# VisualightMicroDIY_032_gnd.net
KiCad netlist of a schematic drawn in EAGLE
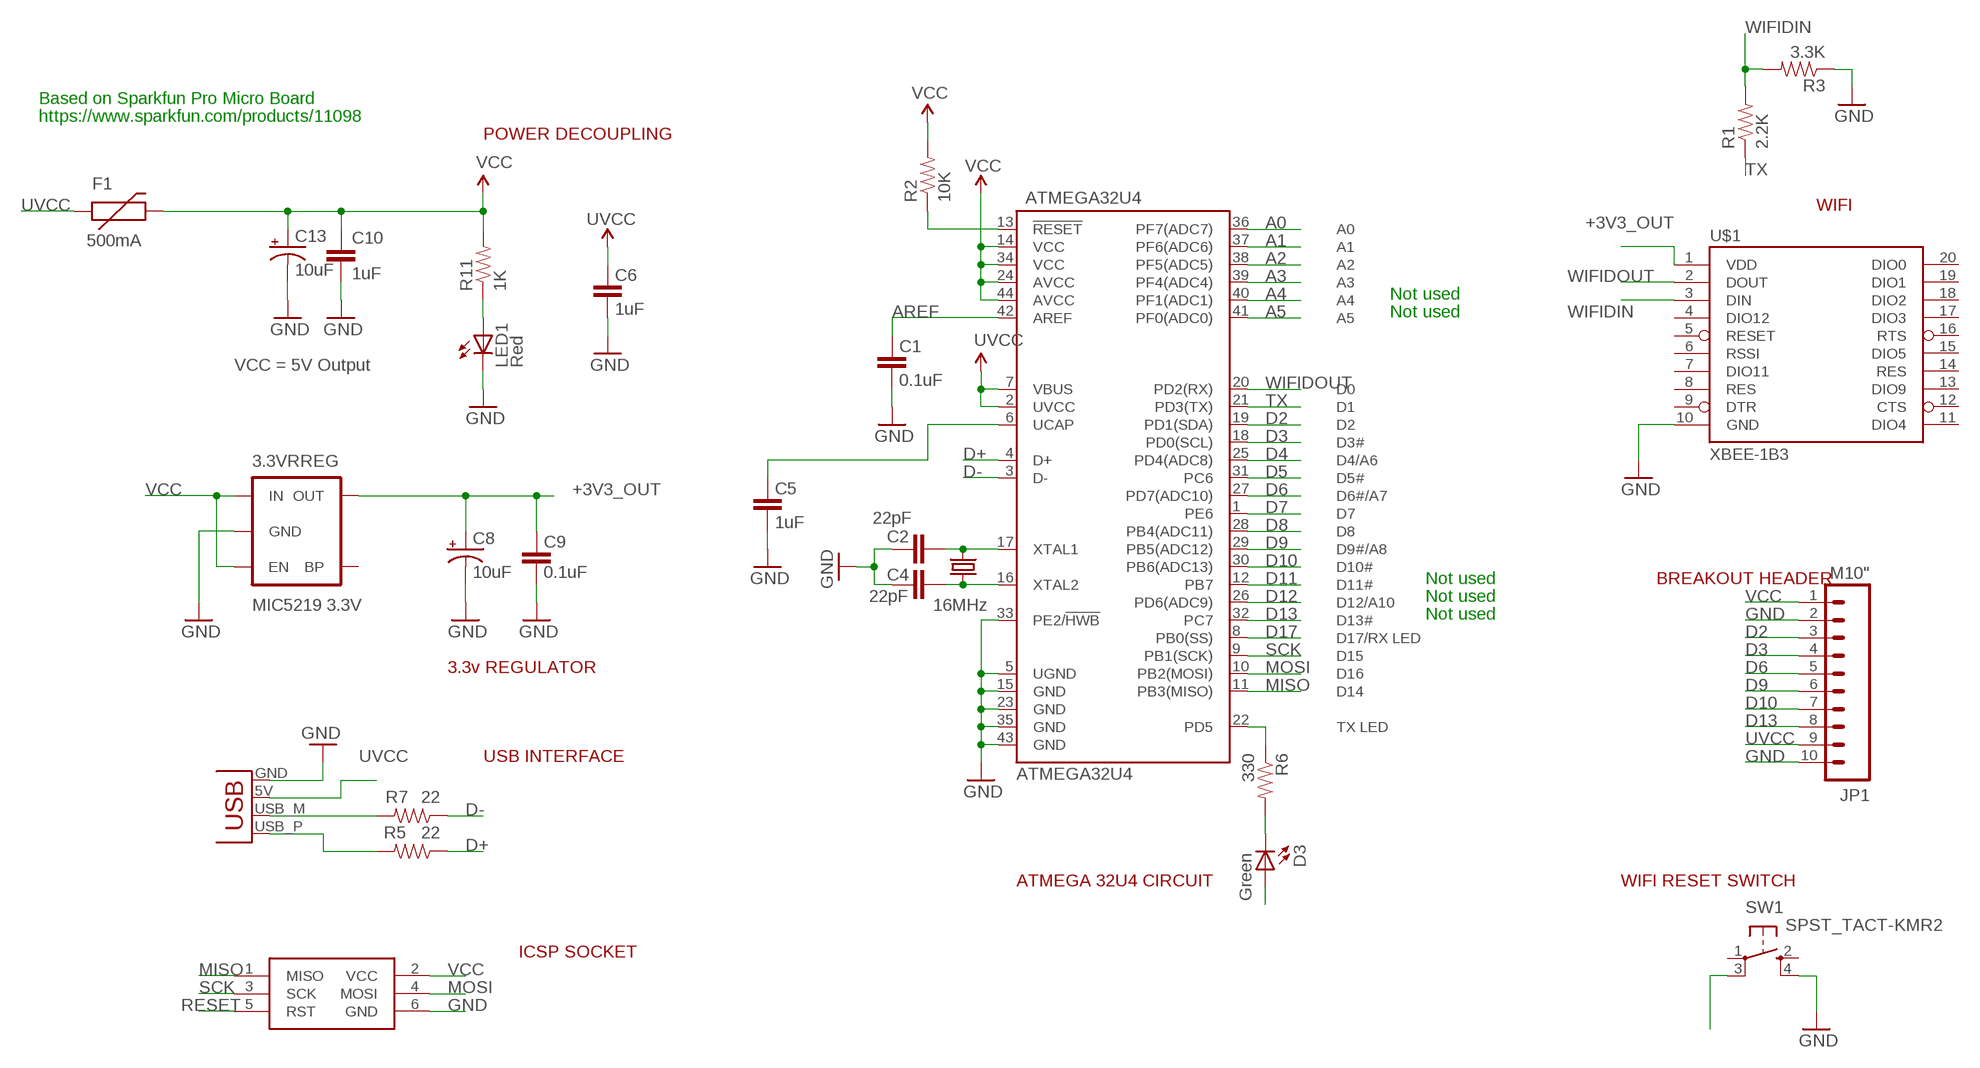
[diagram p0: schematic, sheet 1]

(export (version "E")
  (design (tool "Eeschema 10.0.6"))
  (components
    (comp (ref "3.3VRREG")
      (value "MIC5219 3.3V")
      (footprint "eagle-import:SOT23-5")
      (libsource (lib "eagle-import") (part "V_REG_MIC52193.3V"))
    )
    (comp (ref "ATMEGA32U4")
      (value "ATMEGA32U4")
      (footprint "eagle-import:SPARKFUN-DIGITALIC_TQFP44")
      (libsource (lib "eagle-import") (part "ATMEGA32U4TQFP"))
    )
    (comp (ref "C1")
      (value "0.1uF")
      (footprint "eagle-import:0402-CAP")
      (libsource (lib "eagle-import") (part "CAP0402-CAP"))
    )
    (comp (ref "C2")
      (value "22pF")
      (footprint "eagle-import:0402-CAP")
      (libsource (lib "eagle-import") (part "CAP0402-CAP"))
    )
    (comp (ref "C4")
      (value "22pF")
      (footprint "eagle-import:0402-CAP")
      (libsource (lib "eagle-import") (part "CAP0402-CAP"))
    )
    (comp (ref "C5")
      (value "1uF")
      (footprint "eagle-import:0402-CAP")
      (libsource (lib "eagle-import") (part "CAP0402-CAP"))
    )
    (comp (ref "C6")
      (value "1uF")
      (footprint "eagle-import:0402-CAP")
      (libsource (lib "eagle-import") (part "CAP0402-CAP"))
    )
    (comp (ref "C8")
      (value "10uF")
      (footprint "eagle-import:EIA3216")
      (libsource (lib "eagle-import") (part "CAP_POL1206"))
    )
    (comp (ref "C9")
      (value "0.1uF")
      (footprint "eagle-import:0402-CAP")
      (libsource (lib "eagle-import") (part "CAP0402-CAP"))
    )
    (comp (ref "C10")
      (value "1uF")
      (footprint "eagle-import:0402-CAP")
      (libsource (lib "eagle-import") (part "CAP0402-CAP"))
    )
    (comp (ref "C13")
      (value "10uF")
      (footprint "eagle-import:EIA3216")
      (libsource (lib "eagle-import") (part "CAP_POL1206"))
    )
    (comp (ref "D3")
      (value "Green")
      (footprint "eagle-import:LED-0603")
      (libsource (lib "eagle-import") (part "LED0603"))
    )
    (comp (ref "F1")
      (value "500mA")
      (footprint "eagle-import:PTC-1206")
      (libsource (lib "eagle-import") (part "PTCSMD"))
    )
    (comp (ref "ISP1")
      (value "AVRISP-6")
      (footprint "eagle-import:AVRISP")
      (libsource (lib "eagle-import") (part "AVRISP-6"))
    )
    (comp (ref "JP1")
      (value "M10\"")
      (footprint "eagle-import:1X10")
      (libsource (lib "eagle-import") (part "M10{dblquote}"))
    )
    (comp (ref "LED1")
      (value "Red")
      (footprint "eagle-import:LED-0603")
      (libsource (lib "eagle-import") (part "LED0603"))
    )
    (comp (ref "R1")
      (value "2.2K")
      (footprint "eagle-import:0402-RES")
      (libsource (lib "eagle-import") (part "RESISTOR0402-RES"))
    )
    (comp (ref "R2")
      (value "10K")
      (footprint "eagle-import:0402-RES")
      (libsource (lib "eagle-import") (part "RESISTOR0402-RES"))
    )
    (comp (ref "R3")
      (value "3.3K")
      (footprint "eagle-import:0402-RES")
      (libsource (lib "eagle-import") (part "RESISTOR0402-RES"))
    )
    (comp (ref "R5")
      (value "22")
      (footprint "eagle-import:0402-RES")
      (libsource (lib "eagle-import") (part "RESISTOR0402-RES"))
    )
    (comp (ref "R6")
      (value "330")
      (footprint "eagle-import:0402-RES")
      (libsource (lib "eagle-import") (part "RESISTOR0402-RES"))
    )
    (comp (ref "R7")
      (value "22")
      (footprint "eagle-import:0402-RES")
      (libsource (lib "eagle-import") (part "RESISTOR0402-RES"))
    )
    (comp (ref "R11")
      (value "1K")
      (footprint "eagle-import:0402-RES")
      (libsource (lib "eagle-import") (part "RESISTOR0402-RES"))
    )
    (comp (ref "SW1")
      (value "SPST_TACT-KMR2")
      (footprint "eagle-import:KMR2")
      (libsource (lib "eagle-import") (part "SPST_TACT-KMR2"))
    )
    (comp (ref "U$1")
      (value "XBEE-1B3")
      (footprint "eagle-import:XBEE-SMD")
      (libsource (lib "eagle-import") (part "XBEE-1B3"))
    )
    (comp (ref "X2")
      (value "USBPCB")
      (footprint "eagle-import:USB-A-PCB")
      (libsource (lib "eagle-import") (part "USBPCB"))
    )
    (comp (ref "Y1")
      (value "16MHz")
      (footprint "eagle-import:CRYSTAL-SMD-5X3")
      (libsource (lib "eagle-import") (part "CRYSTAL5X3"))
    )
  )
  (nets
    (net (code "1") (name "/+3V3_OUT") (class "Default")
      (node (ref "3.3VRREG") (pin "5") (pinfunction "OUT_5") (pintype "passive"))
      (node (ref "C8") (pin "A") (pinfunction "+_A") (pintype "passive"))
      (node (ref "C9") (pin "2") (pinfunction "2_2") (pintype "passive"))
      (node (ref "U$1") (pin "1") (pinfunction "VDD_1") (pintype "power_in"))
    )
    (net (code "2") (name "/A0") (class "Default")
      (node (ref "ATMEGA32U4") (pin "36") (pinfunction "PF7(ADC7)_36") (pintype "bidirectional"))
    )
    (net (code "3") (name "/A1") (class "Default")
      (node (ref "ATMEGA32U4") (pin "37") (pinfunction "PF6(ADC6)_37") (pintype "bidirectional"))
    )
    (net (code "4") (name "/A2") (class "Default")
      (node (ref "ATMEGA32U4") (pin "38") (pinfunction "PF5(ADC5)_38") (pintype "bidirectional"))
    )
    (net (code "5") (name "/A3") (class "Default")
      (node (ref "ATMEGA32U4") (pin "39") (pinfunction "PF4(ADC4)_39") (pintype "bidirectional"))
    )
    (net (code "6") (name "/A4") (class "Default")
      (node (ref "ATMEGA32U4") (pin "40") (pinfunction "PF1(ADC1)_40") (pintype "bidirectional"))
    )
    (net (code "7") (name "/A5") (class "Default")
      (node (ref "ATMEGA32U4") (pin "41") (pinfunction "PF0(ADC0)_41") (pintype "bidirectional"))
    )
    (net (code "8") (name "/AREF") (class "Default")
      (node (ref "ATMEGA32U4") (pin "42") (pinfunction "AREF_42") (pintype "bidirectional"))
      (node (ref "C1") (pin "2") (pinfunction "2_2") (pintype "passive"))
    )
    (net (code "9") (name "/D+") (class "Default")
      (node (ref "ATMEGA32U4") (pin "4") (pinfunction "D+_4") (pintype "bidirectional"))
      (node (ref "R5") (pin "1") (pinfunction "1_1") (pintype "passive"))
    )
    (net (code "10") (name "/D-") (class "Default")
      (node (ref "ATMEGA32U4") (pin "3") (pinfunction "D-_3") (pintype "bidirectional"))
      (node (ref "R7") (pin "1") (pinfunction "1_1") (pintype "passive"))
    )
    (net (code "11") (name "/D2") (class "Default")
      (node (ref "ATMEGA32U4") (pin "19") (pinfunction "PD1(SDA)_19") (pintype "bidirectional"))
      (node (ref "JP1") (pin "3") (pinfunction "3_3") (pintype "passive"))
    )
    (net (code "12") (name "/D3") (class "Default")
      (node (ref "ATMEGA32U4") (pin "18") (pinfunction "PD0(SCL)_18") (pintype "bidirectional"))
      (node (ref "JP1") (pin "4") (pinfunction "4_4") (pintype "passive"))
    )
    (net (code "13") (name "/D4") (class "Default")
      (node (ref "ATMEGA32U4") (pin "25") (pinfunction "PD4(ADC8)_25") (pintype "bidirectional"))
    )
    (net (code "14") (name "/D5") (class "Default")
      (node (ref "ATMEGA32U4") (pin "31") (pinfunction "PC6_31") (pintype "bidirectional"))
    )
    (net (code "15") (name "/D6") (class "Default")
      (node (ref "ATMEGA32U4") (pin "27") (pinfunction "PD7(ADC10)_27") (pintype "bidirectional"))
      (node (ref "JP1") (pin "5") (pinfunction "5_5") (pintype "passive"))
    )
    (net (code "16") (name "/D7") (class "Default")
      (node (ref "ATMEGA32U4") (pin "1") (pinfunction "PE6_1") (pintype "bidirectional"))
      (node (ref "SW1") (pin "3") (pinfunction "P1_3") (pintype "passive"))
    )
    (net (code "17") (name "/D8") (class "Default")
      (node (ref "ATMEGA32U4") (pin "28") (pinfunction "PB4(ADC11)_28") (pintype "bidirectional"))
    )
    (net (code "18") (name "/D9") (class "Default")
      (node (ref "ATMEGA32U4") (pin "29") (pinfunction "PB5(ADC12)_29") (pintype "bidirectional"))
      (node (ref "JP1") (pin "6") (pinfunction "6_6") (pintype "passive"))
    )
    (net (code "19") (name "/D10") (class "Default")
      (node (ref "ATMEGA32U4") (pin "30") (pinfunction "PB6(ADC13)_30") (pintype "bidirectional"))
      (node (ref "JP1") (pin "7") (pinfunction "7_7") (pintype "passive"))
    )
    (net (code "20") (name "/D11") (class "Default")
      (node (ref "ATMEGA32U4") (pin "12") (pinfunction "PB7_12") (pintype "bidirectional"))
    )
    (net (code "21") (name "/D12") (class "Default")
      (node (ref "ATMEGA32U4") (pin "26") (pinfunction "PD6(ADC9)_26") (pintype "bidirectional"))
    )
    (net (code "22") (name "/D13") (class "Default")
      (node (ref "ATMEGA32U4") (pin "32") (pinfunction "PC7_32") (pintype "bidirectional"))
      (node (ref "JP1") (pin "8") (pinfunction "8_8") (pintype "passive"))
    )
    (net (code "23") (name "/D17") (class "Default")
      (node (ref "ATMEGA32U4") (pin "8") (pinfunction "PB0(SS)_8") (pintype "bidirectional"))
    )
    (net (code "24") (name "/MISO") (class "Default")
      (node (ref "ATMEGA32U4") (pin "11") (pinfunction "PB3(MISO)_11") (pintype "bidirectional"))
      (node (ref "ISP1") (pin "1") (pinfunction "MISO_1") (pintype "input"))
    )
    (net (code "25") (name "/MOSI") (class "Default")
      (node (ref "ATMEGA32U4") (pin "10") (pinfunction "PB2(MOSI)_10") (pintype "bidirectional"))
      (node (ref "ISP1") (pin "4") (pinfunction "MOSI_4") (pintype "output"))
    )
    (net (code "26") (name "/RESET") (class "Default")
      (node (ref "ATMEGA32U4") (pin "13") (pinfunction "~{RESET}_13") (pintype "bidirectional"))
      (node (ref "ISP1") (pin "5") (pinfunction "RST_5") (pintype "output"))
      (node (ref "R2") (pin "1") (pinfunction "1_1") (pintype "passive"))
    )
    (net (code "27") (name "/SCK") (class "Default")
      (node (ref "ATMEGA32U4") (pin "9") (pinfunction "PB1(SCK)_9") (pintype "bidirectional"))
      (node (ref "ISP1") (pin "3") (pinfunction "SCK_3") (pintype "output"))
    )
    (net (code "28") (name "/TX") (class "Default")
      (node (ref "ATMEGA32U4") (pin "21") (pinfunction "PD3(TX)_21") (pintype "bidirectional"))
      (node (ref "R1") (pin "1") (pinfunction "1_1") (pintype "passive"))
    )
    (net (code "29") (name "/WIFIDIN") (class "Default")
      (node (ref "R1") (pin "2") (pinfunction "2_2") (pintype "passive"))
      (node (ref "R3") (pin "2") (pinfunction "2_2") (pintype "passive"))
      (node (ref "U$1") (pin "3") (pinfunction "DIN_3") (pintype "input"))
    )
    (net (code "30") (name "/WIFIDOUT") (class "Default")
      (node (ref "ATMEGA32U4") (pin "20") (pinfunction "PD2(RX)_20") (pintype "bidirectional"))
      (node (ref "U$1") (pin "2") (pinfunction "DOUT_2") (pintype "output"))
    )
    (net (code "31") (name "GND") (class "Default")
      (node (ref "3.3VRREG") (pin "2") (pinfunction "GND_2") (pintype "input"))
      (node (ref "ATMEGA32U4") (pin "15") (pinfunction "GND_15") (pintype "bidirectional"))
      (node (ref "ATMEGA32U4") (pin "23") (pinfunction "GND_23") (pintype "bidirectional"))
      (node (ref "ATMEGA32U4") (pin "33") (pinfunction "PE2/~{HWB}_33") (pintype "bidirectional"))
      (node (ref "ATMEGA32U4") (pin "35") (pinfunction "GND_35") (pintype "bidirectional"))
      (node (ref "ATMEGA32U4") (pin "43") (pinfunction "GND_43") (pintype "bidirectional"))
      (node (ref "ATMEGA32U4") (pin "5") (pinfunction "UGND_5") (pintype "bidirectional"))
      (node (ref "C1") (pin "1") (pinfunction "1_1") (pintype "passive"))
      (node (ref "C10") (pin "2") (pinfunction "2_2") (pintype "passive"))
      (node (ref "C13") (pin "C") (pinfunction "-_C") (pintype "passive"))
      (node (ref "C2") (pin "2") (pinfunction "2_2") (pintype "passive"))
      (node (ref "C4") (pin "2") (pinfunction "2_2") (pintype "passive"))
      (node (ref "C5") (pin "1") (pinfunction "1_1") (pintype "passive"))
      (node (ref "C6") (pin "1") (pinfunction "1_1") (pintype "passive"))
      (node (ref "C8") (pin "C") (pinfunction "-_C") (pintype "passive"))
      (node (ref "C9") (pin "1") (pinfunction "1_1") (pintype "passive"))
      (node (ref "ISP1") (pin "6") (pinfunction "GND_6") (pintype "power_in"))
      (node (ref "JP1") (pin "10") (pinfunction "10_10") (pintype "passive"))
      (node (ref "JP1") (pin "2") (pinfunction "2_2") (pintype "passive"))
      (node (ref "LED1") (pin "C") (pinfunction "C_C") (pintype "passive"))
      (node (ref "R3") (pin "1") (pinfunction "1_1") (pintype "passive"))
      (node (ref "SW1") (pin "4") (pinfunction "S1_4") (pintype "passive"))
      (node (ref "U$1") (pin "10") (pinfunction "GND_10") (pintype "power_in"))
      (node (ref "X2") (pin "GND") (pinfunction "GND_GND") (pintype "bidirectional"))
    )
    (net (code "32") (name "Net-(ATMEGA32U4-PD5)") (class "Default")
      (node (ref "ATMEGA32U4") (pin "22") (pinfunction "PD5_22") (pintype "bidirectional"))
      (node (ref "R6") (pin "1") (pinfunction "1_1") (pintype "passive"))
    )
    (net (code "33") (name "Net-(ATMEGA32U4-UCAP)") (class "Default")
      (node (ref "ATMEGA32U4") (pin "6") (pinfunction "UCAP_6") (pintype "bidirectional"))
      (node (ref "C5") (pin "2") (pinfunction "2_2") (pintype "passive"))
    )
    (net (code "34") (name "Net-(ATMEGA32U4-XTAL1)") (class "Default")
      (node (ref "ATMEGA32U4") (pin "17") (pinfunction "XTAL1_17") (pintype "bidirectional"))
      (node (ref "C2") (pin "1") (pinfunction "1_1") (pintype "passive"))
      (node (ref "Y1") (pin "3") (pinfunction "2_3") (pintype "passive"))
    )
    (net (code "35") (name "Net-(ATMEGA32U4-XTAL2)") (class "Default")
      (node (ref "ATMEGA32U4") (pin "16") (pinfunction "XTAL2_16") (pintype "bidirectional"))
      (node (ref "C4") (pin "1") (pinfunction "1_1") (pintype "passive"))
      (node (ref "Y1") (pin "1") (pinfunction "1_1") (pintype "passive"))
    )
    (net (code "36") (name "Net-(D3-PadC)") (class "Default")
      (node (ref "D3") (pin "C") (pinfunction "C_C") (pintype "passive"))
      (node (ref "R6") (pin "2") (pinfunction "2_2") (pintype "passive"))
    )
    (net (code "37") (name "Net-(LED1-PadA)") (class "Default")
      (node (ref "LED1") (pin "A") (pinfunction "A_A") (pintype "passive"))
      (node (ref "R11") (pin "1") (pinfunction "1_1") (pintype "passive"))
    )
    (net (code "38") (name "Net-(X2-D+)") (class "Default")
      (node (ref "R5") (pin "2") (pinfunction "2_2") (pintype "passive"))
      (node (ref "X2") (pin "USB_P") (pinfunction "D+_USB_P") (pintype "bidirectional"))
    )
    (net (code "39") (name "Net-(X2-D-)") (class "Default")
      (node (ref "R7") (pin "2") (pinfunction "2_2") (pintype "passive"))
      (node (ref "X2") (pin "USB_M") (pinfunction "D-_USB_M") (pintype "bidirectional"))
    )
    (net (code "40") (name "UVCC") (class "Default")
      (node (ref "ATMEGA32U4") (pin "2") (pinfunction "UVCC_2") (pintype "bidirectional"))
      (node (ref "ATMEGA32U4") (pin "7") (pinfunction "VBUS_7") (pintype "bidirectional"))
      (node (ref "C6") (pin "2") (pinfunction "2_2") (pintype "passive"))
      (node (ref "F1") (pin "1") (pinfunction "1_1") (pintype "bidirectional"))
      (node (ref "JP1") (pin "9") (pinfunction "9_9") (pintype "passive"))
      (node (ref "X2") (pin "5V") (pinfunction "VBUS_5V") (pintype "bidirectional"))
    )
    (net (code "41") (name "VCC") (class "Default")
      (node (ref "3.3VRREG") (pin "1") (pinfunction "IN_1") (pintype "input"))
      (node (ref "3.3VRREG") (pin "3") (pinfunction "EN_3") (pintype "input"))
      (node (ref "ATMEGA32U4") (pin "14") (pinfunction "VCC_14") (pintype "bidirectional"))
      (node (ref "ATMEGA32U4") (pin "24") (pinfunction "AVCC_24") (pintype "bidirectional"))
      (node (ref "ATMEGA32U4") (pin "34") (pinfunction "VCC_34") (pintype "bidirectional"))
      (node (ref "ATMEGA32U4") (pin "44") (pinfunction "AVCC_44") (pintype "bidirectional"))
      (node (ref "C10") (pin "1") (pinfunction "1_1") (pintype "passive"))
      (node (ref "C13") (pin "A") (pinfunction "+_A") (pintype "passive"))
      (node (ref "D3") (pin "A") (pinfunction "A_A") (pintype "passive"))
      (node (ref "F1") (pin "2") (pinfunction "2_2") (pintype "bidirectional"))
      (node (ref "ISP1") (pin "2") (pinfunction "VCC_2") (pintype "power_in"))
      (node (ref "JP1") (pin "1") (pinfunction "1_1") (pintype "passive"))
      (node (ref "R11") (pin "2") (pinfunction "2_2") (pintype "passive"))
      (node (ref "R2") (pin "2") (pinfunction "2_2") (pintype "passive"))
    )
    (net (code "42") (name "unconnected-(3.3VRREG-BP-Pad4)") (class "Default")
      (node (ref "3.3VRREG") (pin "4") (pinfunction "BP_4") (pintype "input"))
    )
    (net (code "43") (name "unconnected-(SW1-P-Pad1)") (class "Default")
      (node (ref "SW1") (pin "1") (pinfunction "P_1") (pintype "passive"))
    )
    (net (code "44") (name "unconnected-(SW1-S-Pad2)") (class "Default")
      (node (ref "SW1") (pin "2") (pinfunction "S_2") (pintype "passive"))
    )
    (net (code "45") (name "unconnected-(U$1-CTS-Pad12)") (class "Default")
      (node (ref "U$1") (pin "12") (pinfunction "CTS_12") (pintype "output"))
    )
    (net (code "46") (name "unconnected-(U$1-DIO0-Pad20)") (class "Default")
      (node (ref "U$1") (pin "20") (pinfunction "DIO0_20") (pintype "bidirectional"))
    )
    (net (code "47") (name "unconnected-(U$1-DIO1-Pad19)") (class "Default")
      (node (ref "U$1") (pin "19") (pinfunction "DIO1_19") (pintype "bidirectional"))
    )
    (net (code "48") (name "unconnected-(U$1-DIO2-Pad18)") (class "Default")
      (node (ref "U$1") (pin "18") (pinfunction "DIO2_18") (pintype "bidirectional"))
    )
    (net (code "49") (name "unconnected-(U$1-DIO3-Pad17)") (class "Default")
      (node (ref "U$1") (pin "17") (pinfunction "DIO3_17") (pintype "bidirectional"))
    )
    (net (code "50") (name "unconnected-(U$1-DIO4-Pad11)") (class "Default")
      (node (ref "U$1") (pin "11") (pinfunction "DIO4_11") (pintype "bidirectional"))
    )
    (net (code "51") (name "unconnected-(U$1-DIO5-Pad15)") (class "Default")
      (node (ref "U$1") (pin "15") (pinfunction "DIO5_15") (pintype "bidirectional"))
    )
    (net (code "52") (name "unconnected-(U$1-DIO9-Pad13)") (class "Default")
      (node (ref "U$1") (pin "13") (pinfunction "DIO9_13") (pintype "bidirectional"))
    )
    (net (code "53") (name "unconnected-(U$1-DIO11-Pad7)") (class "Default")
      (node (ref "U$1") (pin "7") (pinfunction "DIO11_7") (pintype "bidirectional"))
    )
    (net (code "54") (name "unconnected-(U$1-DIO12-Pad4)") (class "Default")
      (node (ref "U$1") (pin "4") (pinfunction "DIO12_4") (pintype "bidirectional"))
    )
    (net (code "55") (name "unconnected-(U$1-DTR-Pad9)") (class "Default")
      (node (ref "U$1") (pin "9") (pinfunction "DTR_9") (pintype "bidirectional"))
    )
    (net (code "56") (name "unconnected-(U$1-RES-Pad8)") (class "Default")
      (node (ref "U$1") (pin "8") (pinfunction "RES_8") (pintype "bidirectional"))
    )
    (net (code "57") (name "unconnected-(U$1-RES-Pad14)") (class "Default")
      (node (ref "U$1") (pin "14") (pinfunction "RES_14") (pintype "bidirectional"))
    )
    (net (code "58") (name "unconnected-(U$1-RESET-Pad5)") (class "Default")
      (node (ref "U$1") (pin "5") (pinfunction "RESET_5") (pintype "input"))
    )
    (net (code "59") (name "unconnected-(U$1-RSSI-Pad6)") (class "Default")
      (node (ref "U$1") (pin "6") (pinfunction "RSSI_6") (pintype "bidirectional"))
    )
    (net (code "60") (name "unconnected-(U$1-RTS-Pad16)") (class "Default")
      (node (ref "U$1") (pin "16") (pinfunction "RTS_16") (pintype "input"))
    )
  )
)
